# openmv3.net
KiCad netlist of a schematic drawn in EAGLE
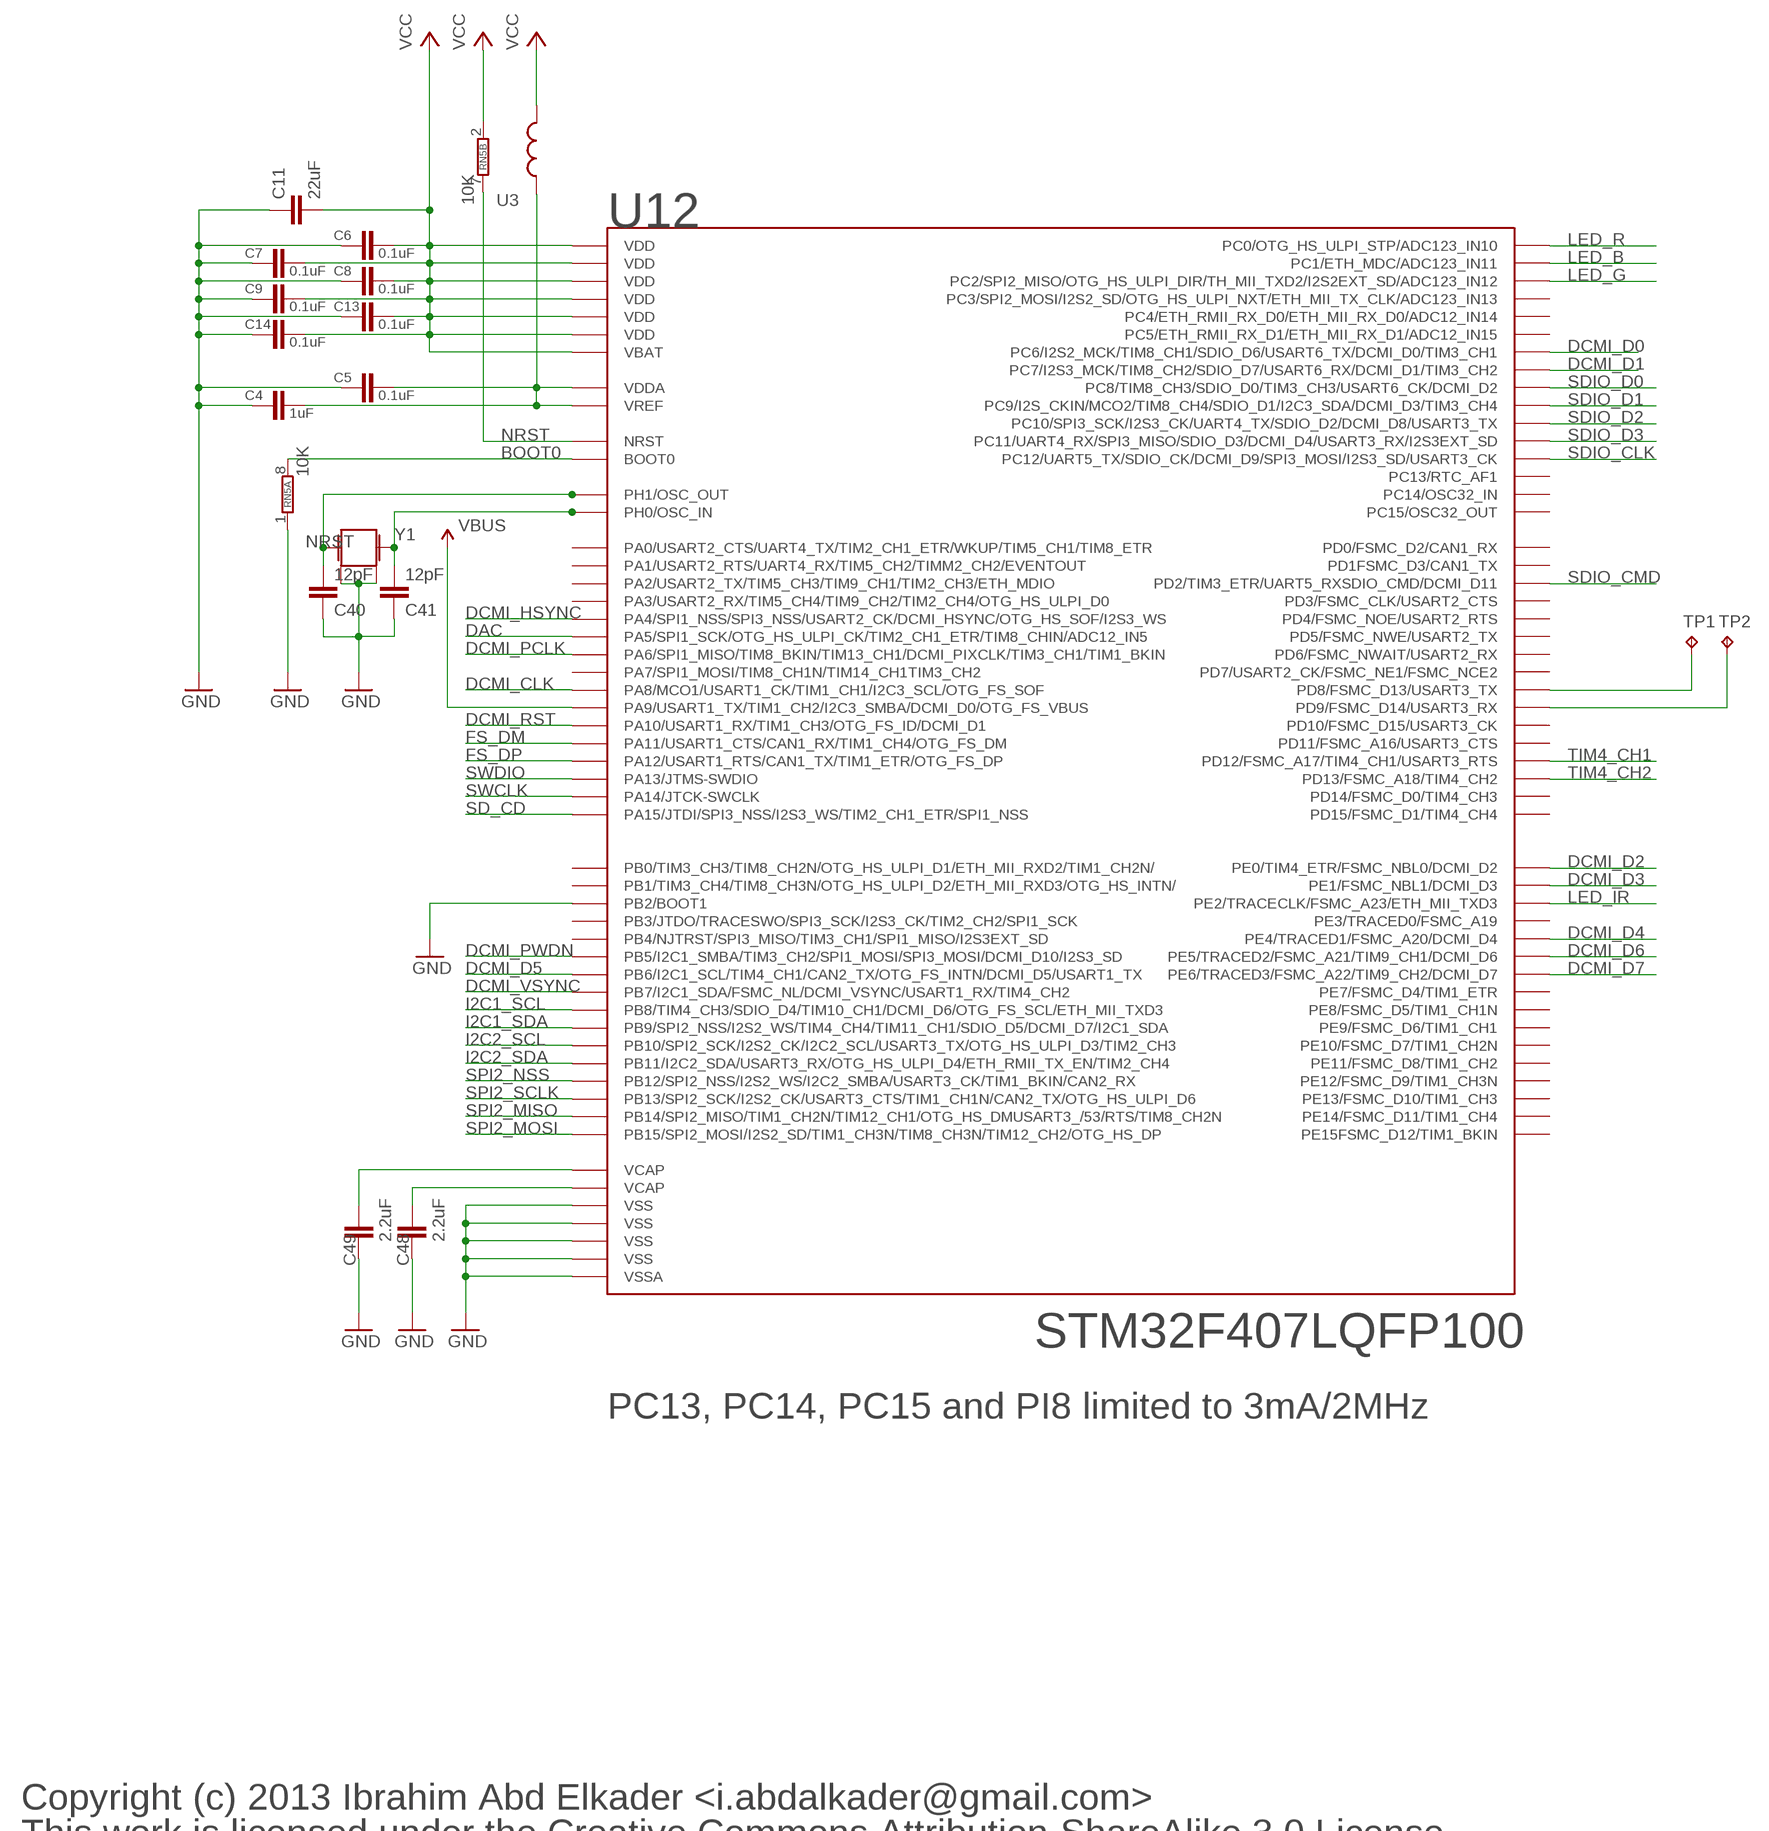
[diagram p0: schematic, sheet 1, part 1 of 2]
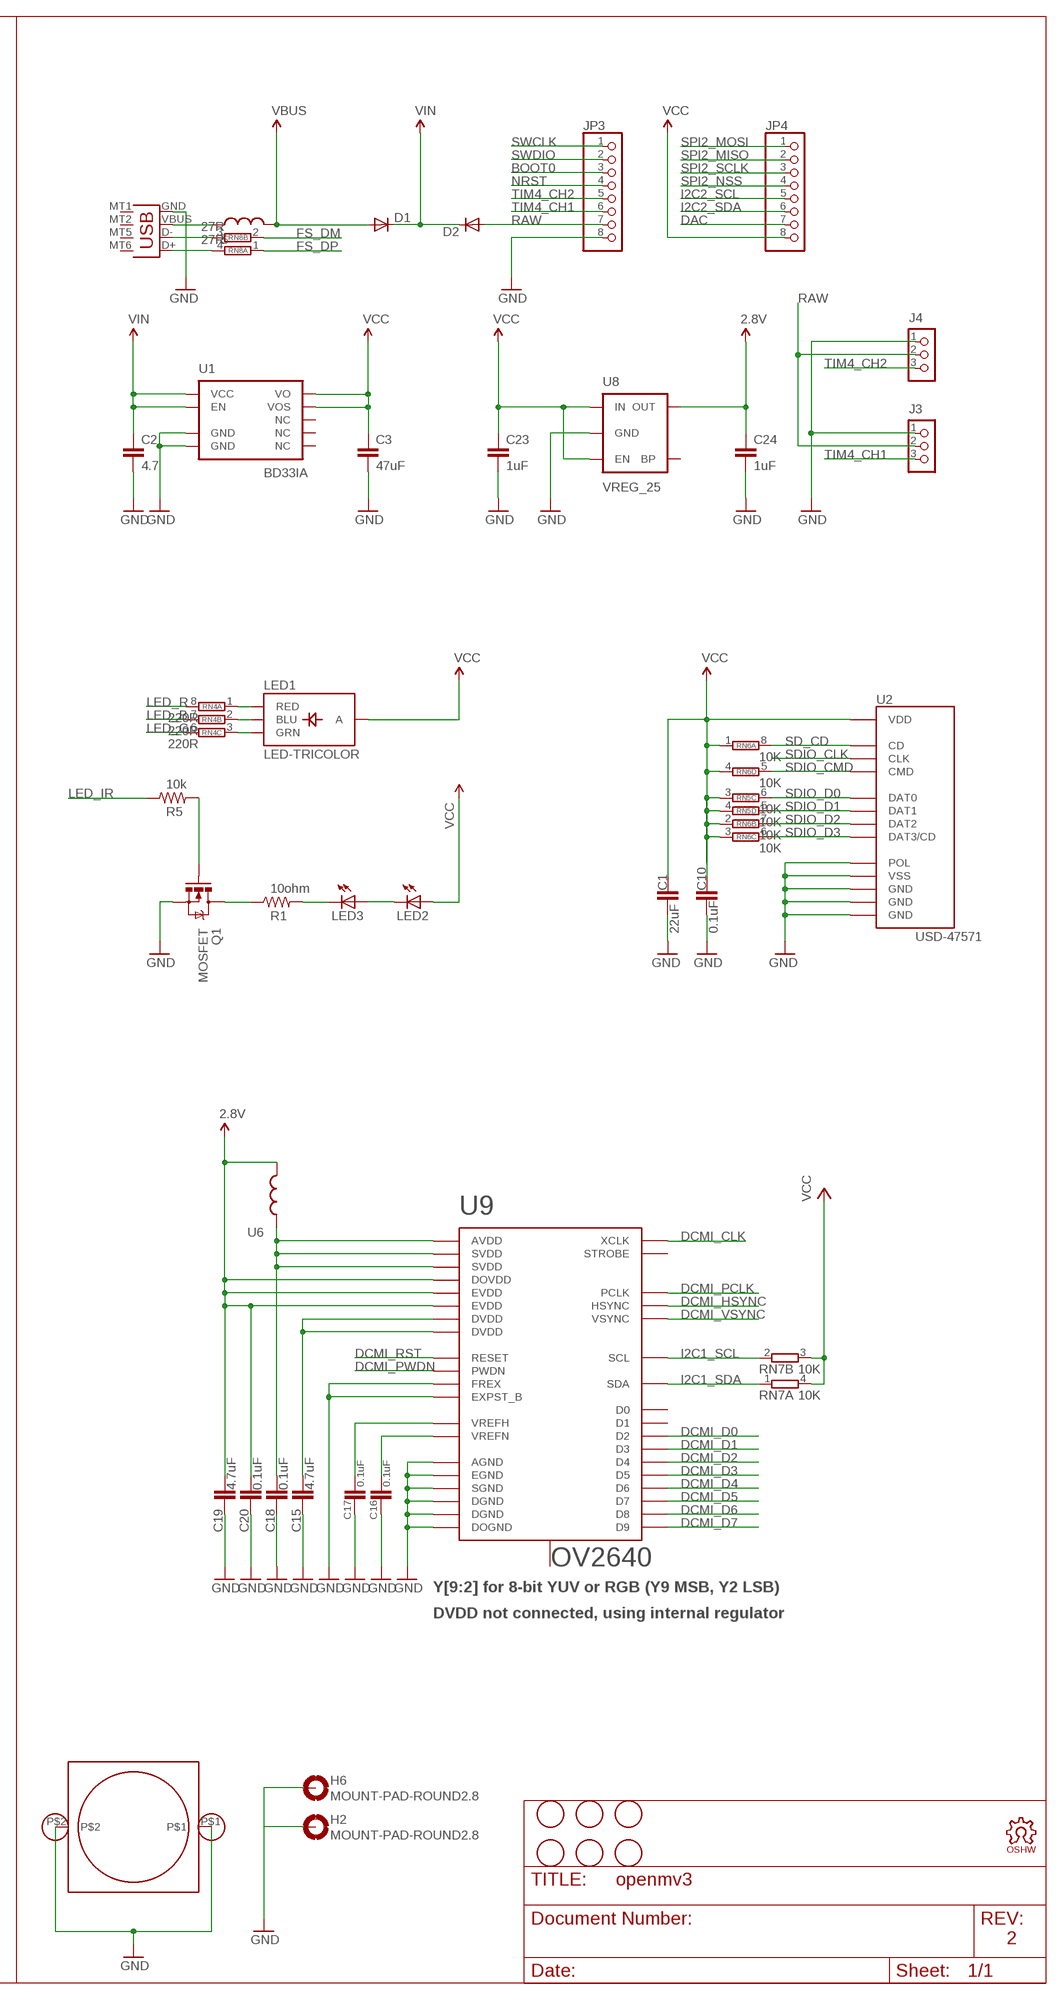
[diagram p1: schematic, sheet 1, part 2 of 2]

(export (version "E")
  (design (tool "Eeschema 10.0.6"))
  (components
    (comp (ref "C1")
      (value "22uF")
      (footprint "eagle-import:0805")
      (libsource (lib "eagle-import") (part "CAP0805"))
    )
    (comp (ref "C2")
      (value "4.7")
      (footprint "eagle-import:0603-CAP")
      (libsource (lib "eagle-import") (part "CAP0603-CAP"))
    )
    (comp (ref "C3")
      (value "47uF")
      (footprint "eagle-import:1206")
      (libsource (lib "eagle-import") (part "CAP1206"))
    )
    (comp (ref "C4")
      (value "1uF")
      (footprint "eagle-import:0603-CAP")
      (libsource (lib "eagle-import") (part "CAP0603-CAP"))
    )
    (comp (ref "C5")
      (value "0.1uF")
      (footprint "eagle-import:0603-CAP")
      (libsource (lib "eagle-import") (part "CAP0603-CAP"))
    )
    (comp (ref "C6")
      (value "0.1uF")
      (footprint "eagle-import:0603-CAP")
      (libsource (lib "eagle-import") (part "CAP0603-CAP"))
    )
    (comp (ref "C7")
      (value "0.1uF")
      (footprint "eagle-import:0603-CAP")
      (libsource (lib "eagle-import") (part "CAP0603-CAP"))
    )
    (comp (ref "C8")
      (value "0.1uF")
      (footprint "eagle-import:0603-CAP")
      (libsource (lib "eagle-import") (part "CAP0603-CAP"))
    )
    (comp (ref "C9")
      (value "0.1uF")
      (footprint "eagle-import:0603-CAP")
      (libsource (lib "eagle-import") (part "CAP0603-CAP"))
    )
    (comp (ref "C10")
      (value "0.1uF")
      (footprint "eagle-import:0603-CAP")
      (libsource (lib "eagle-import") (part "CAP0603-CAP"))
    )
    (comp (ref "C11")
      (value "22uF")
      (footprint "eagle-import:0805")
      (libsource (lib "eagle-import") (part "CAP0805"))
    )
    (comp (ref "C13")
      (value "0.1uF")
      (footprint "eagle-import:0603-CAP")
      (libsource (lib "eagle-import") (part "CAP0603-CAP"))
    )
    (comp (ref "C14")
      (value "0.1uF")
      (footprint "eagle-import:0603-CAP")
      (libsource (lib "eagle-import") (part "CAP0603-CAP"))
    )
    (comp (ref "C15")
      (value "4.7uF")
      (footprint "eagle-import:0603-CAP")
      (libsource (lib "eagle-import") (part "CAP0603-CAP"))
    )
    (comp (ref "C16")
      (value "0.1uF")
      (footprint "eagle-import:0603-CAP")
      (libsource (lib "eagle-import") (part "CAP0603-CAP"))
    )
    (comp (ref "C17")
      (value "0.1uF")
      (footprint "eagle-import:0603-CAP")
      (libsource (lib "eagle-import") (part "CAP0603-CAP"))
    )
    (comp (ref "C18")
      (value "0.1uF")
      (footprint "eagle-import:0603-CAP")
      (libsource (lib "eagle-import") (part "CAP0603-CAP"))
    )
    (comp (ref "C19")
      (value "4.7uF")
      (footprint "eagle-import:0603-CAP")
      (libsource (lib "eagle-import") (part "CAP0603-CAP"))
    )
    (comp (ref "C20")
      (value "0.1uF")
      (footprint "eagle-import:0603-CAP")
      (libsource (lib "eagle-import") (part "CAP0603-CAP"))
    )
    (comp (ref "C23")
      (value "1uF")
      (footprint "eagle-import:0603-CAP")
      (libsource (lib "eagle-import") (part "CAP0603-CAP"))
    )
    (comp (ref "C24")
      (value "1uF")
      (footprint "eagle-import:0603-CAP")
      (libsource (lib "eagle-import") (part "CAP0603-CAP"))
    )
    (comp (ref "C40")
      (value "12pF")
      (footprint "eagle-import:0603-CAP")
      (libsource (lib "eagle-import") (part "CAP0603-CAP"))
    )
    (comp (ref "C41")
      (value "12pF")
      (footprint "eagle-import:0603-CAP")
      (libsource (lib "eagle-import") (part "CAP0603-CAP"))
    )
    (comp (ref "C48")
      (value "2.2uF")
      (footprint "eagle-import:0603-CAP")
      (libsource (lib "eagle-import") (part "CAP0603-CAP"))
    )
    (comp (ref "C49")
      (value "2.2uF")
      (footprint "eagle-import:0603-CAP")
      (libsource (lib "eagle-import") (part "CAP0603-CAP"))
    )
    (comp (ref "D1")
      (value "DIODESOD")
      (footprint "eagle-import:SOD-323")
      (libsource (lib "eagle-import") (part "DIODESOD"))
    )
    (comp (ref "D2")
      (value "DIODESOD")
      (footprint "eagle-import:SOD-323")
      (libsource (lib "eagle-import") (part "DIODESOD"))
    )
    (comp (ref "H2")
      (value "MOUNT-PAD-ROUND2.8")
      (footprint "eagle-import:2,8-PAD")
      (libsource (lib "eagle-import") (part "MOUNT-PAD-ROUND2.8"))
    )
    (comp (ref "H6")
      (value "MOUNT-PAD-ROUND2.8")
      (footprint "eagle-import:2,8-PAD")
      (libsource (lib "eagle-import") (part "MOUNT-PAD-ROUND2.8"))
    )
    (comp (ref "J3")
      (value "CON_HEADER_1X03")
      (footprint "eagle-import:M1X3_SMD")
      (libsource (lib "eagle-import") (part "CON_HEADER_1X03"))
    )
    (comp (ref "J4")
      (value "CON_HEADER_1X03")
      (footprint "eagle-import:M1X3_SMD")
      (libsource (lib "eagle-import") (part "CON_HEADER_1X03"))
    )
    (comp (ref "JP3")
      (value "PINHD-1X8")
      (footprint "eagle-import:1X08")
      (libsource (lib "eagle-import") (part "PINHD-1X8"))
    )
    (comp (ref "JP4")
      (value "PINHD-1X8")
      (footprint "eagle-import:1X08")
      (libsource (lib "eagle-import") (part "PINHD-1X8"))
    )
    (comp (ref "LED1")
      (value "LED-TRICOLOR")
      (footprint "eagle-import:LED-TRICOLOR-SMD")
      (libsource (lib "eagle-import") (part "LED-TRICOLOR"))
    )
    (comp (ref "LED2")
      (value "LED3MM")
      (footprint "eagle-import:LED3MM")
      (libsource (lib "eagle-import") (part "LED3MM"))
    )
    (comp (ref "LED3")
      (value "LED3MM")
      (footprint "eagle-import:LED3MM")
      (libsource (lib "eagle-import") (part "LED3MM"))
    )
    (comp (ref "LOGO1")
      (value "OSHW_LOGO_FILLX0150-NT")
      (footprint "eagle-import:OSHW_FILLX150_NOTEXT")
      (libsource (lib "eagle-import") (part "OSHW_LOGO_FILLX0150-NT"))
    )
    (comp (ref "Q1")
      (value "MOSFET")
      (footprint "eagle-import:SOT23-3")
      (libsource (lib "eagle-import") (part "MOSFET-NCHANNELSMD"))
    )
    (comp (ref "R1")
      (value "10ohm")
      (footprint "eagle-import:0603-RES")
      (libsource (lib "eagle-import") (part "RESISTOR0603-RES"))
    )
    (comp (ref "R5")
      (value "10k")
      (footprint "eagle-import:0603-RES")
      (libsource (lib "eagle-import") (part "RESISTOR0603-RES"))
    )
    (comp (ref "RN4")
      (value "220R")
      (footprint "eagle-import:EXBV8V")
      (fields (field (name "OC_FARNELL") "unknown") (field (name "OC_NEWARK") "unknown"))
      (libsource (lib "eagle-import") (part "4R-NEXBV8V"))
    )
    (comp (ref "RN5")
      (value "10K")
      (footprint "eagle-import:EXBV8V")
      (fields (field (name "OC_FARNELL") "unknown") (field (name "OC_NEWARK") "unknown"))
      (libsource (lib "eagle-import") (part "4R-NEXBV8V"))
    )
    (comp (ref "RN6")
      (value "10K")
      (footprint "eagle-import:EXBV8V")
      (fields (field (name "OC_FARNELL") "unknown") (field (name "OC_NEWARK") "unknown"))
      (libsource (lib "eagle-import") (part "4R-NEXBV8V"))
    )
    (comp (ref "RN7")
      (value "10K")
      (footprint "eagle-import:EXBV4V")
      (libsource (lib "eagle-import") (part "2R-NEXBV4V"))
    )
    (comp (ref "RN8")
      (value "27R")
      (footprint "eagle-import:EXBV4V")
      (libsource (lib "eagle-import") (part "2R-NEXBV4V"))
    )
    (comp (ref "TP1")
      (value "TPTP12R")
      (footprint "eagle-import:TP12R")
      (libsource (lib "eagle-import") (part "TPTP12R"))
    )
    (comp (ref "TP2")
      (value "TPTP12R")
      (footprint "eagle-import:TP12R")
      (libsource (lib "eagle-import") (part "TPTP12R"))
    )
    (comp (ref "U$1")
      (value "LENSMOUNT20MM")
      (footprint "eagle-import:LENSMOUNT-20MM")
      (libsource (lib "eagle-import") (part "LENSMOUNT20MM"))
    )
    (comp (ref "U$14")
      (value "FIDUCIAL")
      (footprint "eagle-import:FIDUCIAL_1MM")
      (libsource (lib "eagle-import") (part "FIDUCIAL"))
    )
    (comp (ref "U$15")
      (value "FIDUCIAL")
      (footprint "eagle-import:FIDUCIAL_1MM")
      (libsource (lib "eagle-import") (part "FIDUCIAL"))
    )
    (comp (ref "U$16")
      (value "FIDUCIAL")
      (footprint "eagle-import:FIDUCIAL_1MM")
      (libsource (lib "eagle-import") (part "FIDUCIAL"))
    )
    (comp (ref "U$17")
      (value "FIDUCIAL")
      (footprint "eagle-import:FIDUCIAL_1MM")
      (libsource (lib "eagle-import") (part "FIDUCIAL"))
    )
    (comp (ref "U$19")
      (value "FIDUCIAL")
      (footprint "eagle-import:FIDUCIAL_1MM")
      (libsource (lib "eagle-import") (part "FIDUCIAL"))
    )
    (comp (ref "U$20")
      (value "FIDUCIAL")
      (footprint "eagle-import:FIDUCIAL_1MM")
      (libsource (lib "eagle-import") (part "FIDUCIAL"))
    )
    (comp (ref "U1")
      (value "BD33IA")
      (footprint "eagle-import:HTSOP-J8")
      (libsource (lib "eagle-import") (part "BD33IA"))
    )
    (comp (ref "U2")
      (value "USD-47571")
      (footprint "eagle-import:USD-47571")
      (libsource (lib "eagle-import") (part "USD-47571"))
    )
    (comp (ref "U3")
      (value "INDUCTOR0603")
      (footprint "eagle-import:0603")
      (libsource (lib "eagle-import") (part "INDUCTOR0603"))
    )
    (comp (ref "U6")
      (value "INDUCTOR0603")
      (footprint "eagle-import:0603")
      (libsource (lib "eagle-import") (part "INDUCTOR0603"))
    )
    (comp (ref "U7")
      (value "INDUCTOR0603")
      (footprint "eagle-import:0603")
      (libsource (lib "eagle-import") (part "INDUCTOR0603"))
    )
    (comp (ref "U8")
      (value "VREG_25")
      (footprint "eagle-import:SOT23-5")
      (libsource (lib "eagle-import") (part "V_REG_LDOSMD"))
    )
    (comp (ref "U9")
      (value "OV2640")
      (footprint "eagle-import:CSP2")
      (libsource (lib "eagle-import") (part "OV2640"))
    )
    (comp (ref "U12")
      (value "STM32F407LQFP100")
      (footprint "eagle-import:LQFP100")
      (libsource (lib "eagle-import") (part "STM32F407LQFP100"))
    )
    (comp (ref "X2")
      (value "USB-MICROB")
      (footprint "eagle-import:USB-MICROB")
      (libsource (lib "eagle-import") (part "USB-MICROB"))
    )
    (comp (ref "Y1")
      (value "CRYSTAL2.5X2.0")
      (footprint "eagle-import:CRYSTAL-2.5X2.0")
      (libsource (lib "eagle-import") (part "CRYSTAL2.5X2.0"))
    )
  )
  (nets
    (net (code "1") (name "/BOOT0") (class "Default")
      (node (ref "JP3") (pin "3") (pinfunction "3_3") (pintype "passive"))
      (node (ref "RN5") (pin "8") (pinfunction "2_8") (pintype "passive"))
      (node (ref "U12") (pin "94") (pinfunction "BOOT0_94") (pintype "bidirectional"))
    )
    (net (code "2") (name "/DAC") (class "Default")
      (node (ref "JP4") (pin "7") (pinfunction "7_7") (pintype "passive"))
      (node (ref "U12") (pin "30") (pinfunction "PA5/SPI1_SCK/OTG_HS_ULPI_CK/TIM2_CH1_ETR/TIM8_CHIN/ADC12_IN5_30") (pintype "bidirectional"))
    )
    (net (code "3") (name "/DCMI_CLK") (class "Default")
      (node (ref "U12") (pin "67") (pinfunction "PA8/MCO1/USART1_CK/TIM1_CH1/I2C3_SCL/OTG_FS_SOF_67") (pintype "bidirectional"))
      (node (ref "U9") (pin "C4") (pinfunction "XCLK_C4") (pintype "bidirectional"))
    )
    (net (code "4") (name "/DCMI_D0") (class "Default")
      (node (ref "U12") (pin "63") (pinfunction "PC6/I2S2_MCK/TIM8_CH1/SDIO_D6/USART6_TX/DCMI_D0/TIM3_CH1_63") (pintype "bidirectional"))
      (node (ref "U9") (pin "F3") (pinfunction "D2_F3") (pintype "bidirectional"))
    )
    (net (code "5") (name "/DCMI_D1") (class "Default")
      (node (ref "U12") (pin "64") (pinfunction "PC7/I2S3_MCK/TIM8_CH2/SDIO_D7/USART6_RX/DCMI_D1/TIM3_CH2_64") (pintype "bidirectional"))
      (node (ref "U9") (pin "G3") (pinfunction "D3_G3") (pintype "bidirectional"))
    )
    (net (code "6") (name "/DCMI_D2") (class "Default")
      (node (ref "U12") (pin "97") (pinfunction "PE0/TIM4_ETR/FSMC_NBL0/DCMI_D2_97") (pintype "bidirectional"))
      (node (ref "U9") (pin "F4") (pinfunction "D4_F4") (pintype "bidirectional"))
    )
    (net (code "7") (name "/DCMI_D3") (class "Default")
      (node (ref "U12") (pin "98") (pinfunction "PE1/FSMC_NBL1/DCMI_D3_98") (pintype "bidirectional"))
      (node (ref "U9") (pin "G4") (pinfunction "D5_G4") (pintype "bidirectional"))
    )
    (net (code "8") (name "/DCMI_D4") (class "Default")
      (node (ref "U12") (pin "3") (pinfunction "PE4/TRACED1/FSMC_A20/DCMI_D4_3") (pintype "bidirectional"))
      (node (ref "U9") (pin "E5") (pinfunction "D6_E5") (pintype "bidirectional"))
    )
    (net (code "9") (name "/DCMI_D5") (class "Default")
      (node (ref "U12") (pin "92") (pinfunction "PB6/I2C1_SCL/TIM4_CH1/CAN2_TX/OTG_FS_INTN/DCMI_D5/USART1_TX_92") (pintype "bidirectional"))
      (node (ref "U9") (pin "G5") (pinfunction "D7_G5") (pintype "bidirectional"))
    )
    (net (code "10") (name "/DCMI_D6") (class "Default")
      (node (ref "U12") (pin "4") (pinfunction "PE5/TRACED2/FSMC_A21/TIM9_CH1/DCMI_D6_4") (pintype "bidirectional"))
      (node (ref "U9") (pin "F5") (pinfunction "D8_F5") (pintype "bidirectional"))
    )
    (net (code "11") (name "/DCMI_D7") (class "Default")
      (node (ref "U12") (pin "5") (pinfunction "PE6/TRACED3/FSMC_A22/TIM9_CH2/DCMI_D7_5") (pintype "bidirectional"))
      (node (ref "U9") (pin "G6") (pinfunction "D9_G6") (pintype "bidirectional"))
    )
    (net (code "12") (name "/DCMI_HSYNC") (class "Default")
      (node (ref "U12") (pin "29") (pinfunction "PA4/SPI1_NSS/SPI3_NSS/USART2_CK/DCMI_HSYNC/OTG_HS_SOF/I2S3_WS_29") (pintype "bidirectional"))
      (node (ref "U9") (pin "C3") (pinfunction "HSYNC_C3") (pintype "bidirectional"))
    )
    (net (code "13") (name "/DCMI_PCLK") (class "Default")
      (node (ref "U12") (pin "31") (pinfunction "PA6/SPI1_MISO/TIM8_BKIN/TIM13_CH1/DCMI_PIXCLK/TIM3_CH1/TIM1_BKIN_31") (pintype "bidirectional"))
      (node (ref "U9") (pin "E3") (pinfunction "PCLK_E3") (pintype "bidirectional"))
    )
    (net (code "14") (name "/DCMI_PWDN") (class "Default")
      (node (ref "U12") (pin "91") (pinfunction "PB5/I2C1_SMBA/TIM3_CH2/SPI1_MOSI/SPI3_MOSI/DCMI_D10/I2S3_SD_91") (pintype "bidirectional"))
      (node (ref "U9") (pin "B6") (pinfunction "PWDN_B6") (pintype "bidirectional"))
    )
    (net (code "15") (name "/DCMI_RST") (class "Default")
      (node (ref "U12") (pin "69") (pinfunction "PA10/USART1_RX/TIM1_CH3/OTG_FS_ID/DCMI_D1_69") (pintype "bidirectional"))
      (node (ref "U9") (pin "C6") (pinfunction "RESET_C6") (pintype "bidirectional"))
    )
    (net (code "16") (name "/DCMI_VSYNC") (class "Default")
      (node (ref "U12") (pin "93") (pinfunction "PB7/I2C1_SDA/FSMC_NL/DCMI_VSYNC/USART1_RX/TIM4_CH2_93") (pintype "bidirectional"))
      (node (ref "U9") (pin "D2") (pinfunction "VSYNC_D2") (pintype "bidirectional"))
    )
    (net (code "17") (name "/FS_DM") (class "Default")
      (node (ref "RN8") (pin "2") (pinfunction "1_2") (pintype "passive"))
      (node (ref "U12") (pin "70") (pinfunction "PA11/USART1_CTS/CAN1_RX/TIM1_CH4/OTG_FS_DM_70") (pintype "bidirectional"))
    )
    (net (code "18") (name "/FS_DP") (class "Default")
      (node (ref "RN8") (pin "1") (pinfunction "1_1") (pintype "passive"))
      (node (ref "U12") (pin "71") (pinfunction "PA12/USART1_RTS/CAN1_TX/TIM1_ETR/OTG_FS_DP_71") (pintype "bidirectional"))
    )
    (net (code "19") (name "/I2C1_SCL") (class "Default")
      (node (ref "RN7") (pin "2") (pinfunction "1_2") (pintype "passive"))
      (node (ref "U12") (pin "95") (pinfunction "PB8/TIM4_CH3/SDIO_D4/TIM10_CH1/DCMI_D6/OTG_FS_SCL/ETH_MII_TXD3_95") (pintype "bidirectional"))
      (node (ref "U9") (pin "C2") (pinfunction "SCL_C2") (pintype "bidirectional"))
    )
    (net (code "20") (name "/I2C1_SDA") (class "Default")
      (node (ref "RN7") (pin "1") (pinfunction "1_1") (pintype "passive"))
      (node (ref "U12") (pin "96") (pinfunction "PB9/SPI2_NSS/I2S2_WS/TIM4_CH4/TIM11_CH1/SDIO_D5/DCMI_D7/I2C1_SDA_96") (pintype "bidirectional"))
      (node (ref "U9") (pin "C1") (pinfunction "SDA_C1") (pintype "bidirectional"))
    )
    (net (code "21") (name "/I2C2_SCL") (class "Default")
      (node (ref "JP4") (pin "5") (pinfunction "5_5") (pintype "passive"))
      (node (ref "U12") (pin "47") (pinfunction "PB10/SPI2_SCK/I2S2_CK/I2C2_SCL/USART3_TX/OTG_HS_ULPI_D3/TIM2_CH3_47") (pintype "bidirectional"))
    )
    (net (code "22") (name "/I2C2_SDA") (class "Default")
      (node (ref "JP4") (pin "6") (pinfunction "6_6") (pintype "passive"))
      (node (ref "U12") (pin "48") (pinfunction "PB11/I2C2_SDA/USART3_RX/OTG_HS_ULPI_D4/ETH_RMII_TX_EN/TIM2_CH4_48") (pintype "bidirectional"))
    )
    (net (code "23") (name "/LED_B") (class "Default")
      (node (ref "RN4") (pin "7") (pinfunction "2_7") (pintype "passive"))
      (node (ref "U12") (pin "16") (pinfunction "PC1/ETH_MDC/ADC123_IN11_16") (pintype "bidirectional"))
    )
    (net (code "24") (name "/LED_G") (class "Default")
      (node (ref "RN4") (pin "6") (pinfunction "2_6") (pintype "passive"))
      (node (ref "U12") (pin "17") (pinfunction "PC2/SPI2_MISO/OTG_HS_ULPI_DIR/TH_MII_TXD2/I2S2EXT_SD/ADC123_IN12_17") (pintype "bidirectional"))
    )
    (net (code "25") (name "/LED_IR") (class "Default")
      (node (ref "R5") (pin "1") (pinfunction "1_1") (pintype "passive"))
      (node (ref "U12") (pin "1") (pinfunction "PE2/TRACECLK/FSMC_A23/ETH_MII_TXD3_1") (pintype "bidirectional"))
    )
    (net (code "26") (name "/LED_R") (class "Default")
      (node (ref "RN4") (pin "8") (pinfunction "2_8") (pintype "passive"))
      (node (ref "U12") (pin "15") (pinfunction "PC0/OTG_HS_ULPI_STP/ADC123_IN10_15") (pintype "bidirectional"))
    )
    (net (code "27") (name "/NRST") (class "Default")
      (node (ref "JP3") (pin "4") (pinfunction "4_4") (pintype "passive"))
      (node (ref "RN5") (pin "7") (pinfunction "2_7") (pintype "passive"))
      (node (ref "U12") (pin "14") (pinfunction "NRST_14") (pintype "bidirectional"))
    )
    (net (code "28") (name "/RAW") (class "Default")
      (node (ref "D2") (pin "2") (pinfunction "A_2") (pintype "passive"))
      (node (ref "J3") (pin "2") (pinfunction "2_2") (pintype "bidirectional"))
      (node (ref "J4") (pin "2") (pinfunction "2_2") (pintype "bidirectional"))
      (node (ref "JP3") (pin "7") (pinfunction "7_7") (pintype "passive"))
    )
    (net (code "29") (name "/SDIO_CLK") (class "Default")
      (node (ref "U12") (pin "80") (pinfunction "PC12/UART5_TX/SDIO_CK/DCMI_D9/SPI3_MOSI/I2S3_SD/USART3_CK_80") (pintype "bidirectional"))
      (node (ref "U2") (pin "P$5") (pinfunction "CLK_P$5") (pintype "bidirectional"))
    )
    (net (code "30") (name "/SDIO_CMD") (class "Default")
      (node (ref "RN6") (pin "5") (pinfunction "2_5") (pintype "passive"))
      (node (ref "U12") (pin "83") (pinfunction "PD2/TIM3_ETR/UART5_RXSDIO_CMD/DCMI_D11_83") (pintype "bidirectional"))
      (node (ref "U2") (pin "P$3") (pinfunction "CMD_P$3") (pintype "bidirectional"))
    )
    (net (code "31") (name "/SDIO_D0") (class "Default")
      (node (ref "RN5") (pin "6") (pinfunction "2_6") (pintype "passive"))
      (node (ref "U12") (pin "65") (pinfunction "PC8/TIM8_CH3/SDIO_D0/TIM3_CH3/USART6_CK/DCMI_D2_65") (pintype "bidirectional"))
      (node (ref "U2") (pin "P$7") (pinfunction "DAT0_P$7") (pintype "bidirectional"))
    )
    (net (code "32") (name "/SDIO_D1") (class "Default")
      (node (ref "RN5") (pin "5") (pinfunction "2_5") (pintype "passive"))
      (node (ref "U12") (pin "66") (pinfunction "PC9/I2S_CKIN/MCO2/TIM8_CH4/SDIO_D1/I2C3_SDA/DCMI_D3/TIM3_CH4_66") (pintype "bidirectional"))
      (node (ref "U2") (pin "P$8") (pinfunction "DAT1_P$8") (pintype "bidirectional"))
    )
    (net (code "33") (name "/SDIO_D2") (class "Default")
      (node (ref "RN6") (pin "7") (pinfunction "2_7") (pintype "passive"))
      (node (ref "U12") (pin "78") (pinfunction "PC10/SPI3_SCK/I2S3_CK/UART4_TX/SDIO_D2/DCMI_D8/USART3_TX_78") (pintype "bidirectional"))
      (node (ref "U2") (pin "P$1") (pinfunction "DAT2_P$1") (pintype "bidirectional"))
    )
    (net (code "34") (name "/SDIO_D3") (class "Default")
      (node (ref "RN6") (pin "6") (pinfunction "2_6") (pintype "passive"))
      (node (ref "U12") (pin "79") (pinfunction "PC11/UART4_RX/SPI3_MISO/SDIO_D3/DCMI_D4/USART3_RX/I2S3EXT_SD_79") (pintype "bidirectional"))
      (node (ref "U2") (pin "P$2") (pinfunction "DAT3/CD_P$2") (pintype "bidirectional"))
    )
    (net (code "35") (name "/SD_CD") (class "Default")
      (node (ref "RN6") (pin "8") (pinfunction "2_8") (pintype "passive"))
      (node (ref "U12") (pin "77") (pinfunction "PA15/JTDI/SPI3_NSS/I2S3_WS/TIM2_CH1_ETR/SPI1_NSS_77") (pintype "bidirectional"))
      (node (ref "U2") (pin "G$5") (pinfunction "CD_G$5") (pintype "power_in"))
    )
    (net (code "36") (name "/SPI2_MISO") (class "Default")
      (node (ref "JP4") (pin "2") (pinfunction "2_2") (pintype "passive"))
      (node (ref "U12") (pin "53") (pinfunction "PB14/SPI2_MISO/TIM1_CH2N/TIM12_CH1/OTG_HS_DMUSART3_/53/RTS/TIM8_CH2N_53") (pintype "bidirectional"))
    )
    (net (code "37") (name "/SPI2_MOSI") (class "Default")
      (node (ref "JP4") (pin "1") (pinfunction "1_1") (pintype "passive"))
      (node (ref "U12") (pin "54") (pinfunction "PB15/SPI2_MOSI/I2S2_SD/TIM1_CH3N/TIM8_CH3N/TIM12_CH2/OTG_HS_DP_54") (pintype "bidirectional"))
    )
    (net (code "38") (name "/SPI2_NSS") (class "Default")
      (node (ref "JP4") (pin "4") (pinfunction "4_4") (pintype "passive"))
      (node (ref "U12") (pin "51") (pinfunction "PB12/SPI2_NSS/I2S2_WS/I2C2_SMBA/USART3_CK/TIM1_BKIN/CAN2_RX_51") (pintype "bidirectional"))
    )
    (net (code "39") (name "/SPI2_SCLK") (class "Default")
      (node (ref "JP4") (pin "3") (pinfunction "3_3") (pintype "passive"))
      (node (ref "U12") (pin "52") (pinfunction "PB13/SPI2_SCK/I2S2_CK/USART3_CTS/TIM1_CH1N/CAN2_TX/OTG_HS_ULPI_D6_52") (pintype "bidirectional"))
    )
    (net (code "40") (name "/SWCLK") (class "Default")
      (node (ref "JP3") (pin "1") (pinfunction "1_1") (pintype "passive"))
      (node (ref "U12") (pin "76") (pinfunction "PA14/JTCK-SWCLK_76") (pintype "bidirectional"))
    )
    (net (code "41") (name "/SWDIO") (class "Default")
      (node (ref "JP3") (pin "2") (pinfunction "2_2") (pintype "passive"))
      (node (ref "U12") (pin "72") (pinfunction "PA13/JTMS-SWDIO_72") (pintype "bidirectional"))
    )
    (net (code "42") (name "/TIM4_CH1") (class "Default")
      (node (ref "J3") (pin "3") (pinfunction "3_3") (pintype "bidirectional"))
      (node (ref "JP3") (pin "6") (pinfunction "6_6") (pintype "passive"))
      (node (ref "U12") (pin "59") (pinfunction "PD12/FSMC_A17/TIM4_CH1/USART3_RTS_59") (pintype "bidirectional"))
    )
    (net (code "43") (name "/TIM4_CH2") (class "Default")
      (node (ref "J4") (pin "3") (pinfunction "3_3") (pintype "bidirectional"))
      (node (ref "JP3") (pin "5") (pinfunction "5_5") (pintype "passive"))
      (node (ref "U12") (pin "60") (pinfunction "PD13/FSMC_A18/TIM4_CH2_60") (pintype "bidirectional"))
    )
    (net (code "44") (name "2.8V") (class "Default")
      (node (ref "C19") (pin "1") (pinfunction "1_1") (pintype "passive"))
      (node (ref "C20") (pin "1") (pinfunction "1_1") (pintype "passive"))
      (node (ref "C24") (pin "1") (pinfunction "1_1") (pintype "passive"))
      (node (ref "U6") (pin "2") (pinfunction "2_2") (pintype "passive"))
      (node (ref "U8") (pin "5") (pinfunction "OUT_5") (pintype "passive"))
      (node (ref "U9") (pin "B1") (pinfunction "DOVDD_B1") (pintype "power_in"))
      (node (ref "U9") (pin "F1") (pinfunction "EVDD_F1") (pintype "power_in"))
      (node (ref "U9") (pin "G1") (pinfunction "EVDD_G1") (pintype "power_in"))
    )
    (net (code "45") (name "GND") (class "Default")
      (node (ref "C1") (pin "2") (pinfunction "2_2") (pintype "passive"))
      (node (ref "C10") (pin "2") (pinfunction "2_2") (pintype "passive"))
      (node (ref "C11") (pin "1") (pinfunction "1_1") (pintype "passive"))
      (node (ref "C13") (pin "2") (pinfunction "2_2") (pintype "passive"))
      (node (ref "C14") (pin "2") (pinfunction "2_2") (pintype "passive"))
      (node (ref "C15") (pin "2") (pinfunction "2_2") (pintype "passive"))
      (node (ref "C16") (pin "2") (pinfunction "2_2") (pintype "passive"))
      (node (ref "C17") (pin "2") (pinfunction "2_2") (pintype "passive"))
      (node (ref "C18") (pin "2") (pinfunction "2_2") (pintype "passive"))
      (node (ref "C19") (pin "2") (pinfunction "2_2") (pintype "passive"))
      (node (ref "C2") (pin "2") (pinfunction "2_2") (pintype "passive"))
      (node (ref "C20") (pin "2") (pinfunction "2_2") (pintype "passive"))
      (node (ref "C23") (pin "2") (pinfunction "2_2") (pintype "passive"))
      (node (ref "C24") (pin "2") (pinfunction "2_2") (pintype "passive"))
      (node (ref "C3") (pin "2") (pinfunction "2_2") (pintype "passive"))
      (node (ref "C4") (pin "2") (pinfunction "2_2") (pintype "passive"))
      (node (ref "C40") (pin "1") (pinfunction "1_1") (pintype "passive"))
      (node (ref "C41") (pin "1") (pinfunction "1_1") (pintype "passive"))
      (node (ref "C48") (pin "2") (pinfunction "2_2") (pintype "passive"))
      (node (ref "C49") (pin "2") (pinfunction "2_2") (pintype "passive"))
      (node (ref "C5") (pin "2") (pinfunction "2_2") (pintype "passive"))
      (node (ref "C6") (pin "2") (pinfunction "2_2") (pintype "passive"))
      (node (ref "C7") (pin "2") (pinfunction "2_2") (pintype "passive"))
      (node (ref "C8") (pin "2") (pinfunction "2_2") (pintype "passive"))
      (node (ref "C9") (pin "2") (pinfunction "2_2") (pintype "passive"))
      (node (ref "H2") (pin "B2,8") (pinfunction "MOUNT_B2,8") (pintype "passive"))
      (node (ref "H6") (pin "B2,8") (pinfunction "MOUNT_B2,8") (pintype "passive"))
      (node (ref "J3") (pin "1") (pinfunction "1_1") (pintype "bidirectional"))
      (node (ref "J4") (pin "1") (pinfunction "1_1") (pintype "bidirectional"))
      (node (ref "JP3") (pin "8") (pinfunction "8_8") (pintype "passive"))
      (node (ref "Q1") (pin "2") (pinfunction "S_2") (pintype "passive"))
      (node (ref "RN5") (pin "1") (pinfunction "1_1") (pintype "passive"))
      (node (ref "U$1") (pin "P$1") (pinfunction "P$1_P$1") (pintype "power_in"))
      (node (ref "U$1") (pin "P$2") (pinfunction "P$2_P$2") (pintype "power_in"))
      (node (ref "U1") (pin "3") (pinfunction "GND_3") (pintype "input"))
      (node (ref "U1") (pin "P$1") (pinfunction "GND_P$1") (pintype "input"))
      (node (ref "U12") (pin "10") (pinfunction "VSS_10") (pintype "power_in"))
      (node (ref "U12") (pin "20") (pinfunction "VSSA_20") (pintype "power_in"))
      (node (ref "U12") (pin "27") (pinfunction "VSS_27") (pintype "power_in"))
      (node (ref "U12") (pin "37") (pinfunction "PB2/BOOT1_37") (pintype "bidirectional"))
      (node (ref "U12") (pin "74") (pinfunction "VSS_74") (pintype "power_in"))
      (node (ref "U12") (pin "99") (pinfunction "VSS_99") (pintype "power_in"))
      (node (ref "U2") (pin "G$1") (pinfunction "GND_G$1") (pintype "power_in"))
      (node (ref "U2") (pin "G$2") (pinfunction "GND_G$2") (pintype "power_in"))
      (node (ref "U2") (pin "G$3") (pinfunction "GND_G$3") (pintype "power_in"))
      (node (ref "U2") (pin "G$4") (pinfunction "POL_G$4") (pintype "power_in"))
      (node (ref "U2") (pin "P$6") (pinfunction "VSS_P$6") (pintype "power_in"))
      (node (ref "U8") (pin "2") (pinfunction "GND_2") (pintype "input"))
      (node (ref "U9") (pin "A1") (pinfunction "DOGND_A1") (pintype "power_in"))
      (node (ref "U9") (pin "A2") (pinfunction "EXPST_B_A2") (pintype "output"))
      (node (ref "U9") (pin "A3") (pinfunction "AGND_A3") (pintype "power_in"))
      (node (ref "U9") (pin "A4") (pinfunction "SGND_A4") (pintype "power_in"))
      (node (ref "U9") (pin "B2") (pinfunction "FREX_B2") (pintype "input"))
      (node (ref "U9") (pin "E4") (pinfunction "EGND_E4") (pintype "power_in"))
      (node (ref "U9") (pin "E6") (pinfunction "DGND_E6") (pintype "power_in"))
      (node (ref "U9") (pin "G2") (pinfunction "DGND_G2") (pintype "power_in"))
      (node (ref "X2") (pin "GND") (pinfunction "GND_GND") (pintype "bidirectional"))
      (node (ref "Y1") (pin "2") (pinfunction "P$1_2") (pintype "power_in"))
      (node (ref "Y1") (pin "4") (pinfunction "P$2_4") (pintype "power_in"))
    )
    (net (code "46") (name "Net-(C15-Pad1)") (class "Default")
      (node (ref "C15") (pin "1") (pinfunction "1_1") (pintype "passive"))
      (node (ref "U9") (pin "F2") (pinfunction "DVDD_F2") (pintype "power_in"))
      (node (ref "U9") (pin "F6") (pinfunction "DVDD_F6") (pintype "power_in"))
    )
    (net (code "47") (name "Net-(C48-Pad1)") (class "Default")
      (node (ref "C48") (pin "1") (pinfunction "1_1") (pintype "passive"))
      (node (ref "U12") (pin "73") (pinfunction "VCAP_73") (pintype "power_in"))
    )
    (net (code "48") (name "Net-(C49-Pad1)") (class "Default")
      (node (ref "C49") (pin "1") (pinfunction "1_1") (pintype "passive"))
      (node (ref "U12") (pin "49") (pinfunction "VCAP_49") (pintype "power_in"))
    )
    (net (code "49") (name "Net-(LED1-BLU)") (class "Default")
      (node (ref "LED1") (pin "B") (pinfunction "BLU_B") (pintype "bidirectional"))
      (node (ref "RN4") (pin "2") (pinfunction "1_2") (pintype "passive"))
    )
    (net (code "50") (name "Net-(LED1-GRN)") (class "Default")
      (node (ref "LED1") (pin "G") (pinfunction "GRN_G") (pintype "bidirectional"))
      (node (ref "RN4") (pin "3") (pinfunction "1_3") (pintype "passive"))
    )
    (net (code "51") (name "Net-(LED1-RED)") (class "Default")
      (node (ref "LED1") (pin "R") (pinfunction "RED_R") (pintype "bidirectional"))
      (node (ref "RN4") (pin "1") (pinfunction "1_1") (pintype "passive"))
    )
    (net (code "52") (name "Net-(LED2-C)") (class "Default")
      (node (ref "LED2") (pin "K") (pinfunction "C_K") (pintype "passive"))
      (node (ref "LED3") (pin "A") (pinfunction "A_A") (pintype "passive"))
    )
    (net (code "53") (name "Net-(LED3-C)") (class "Default")
      (node (ref "LED3") (pin "K") (pinfunction "C_K") (pintype "passive"))
      (node (ref "R1") (pin "2") (pinfunction "2_2") (pintype "passive"))
    )
    (net (code "54") (name "Net-(Q1-D)") (class "Default")
      (node (ref "Q1") (pin "3") (pinfunction "D_3") (pintype "passive"))
      (node (ref "R1") (pin "1") (pinfunction "1_1") (pintype "passive"))
    )
    (net (code "55") (name "Net-(Q1-G)") (class "Default")
      (node (ref "Q1") (pin "1") (pinfunction "G_1") (pintype "passive"))
      (node (ref "R5") (pin "2") (pinfunction "2_2") (pintype "passive"))
    )
    (net (code "56") (name "Net-(RN8A-2)") (class "Default")
      (node (ref "RN8") (pin "4") (pinfunction "2_4") (pintype "passive"))
      (node (ref "X2") (pin "D+") (pinfunction "D+_D+") (pintype "bidirectional"))
    )
    (net (code "57") (name "Net-(RN8B-2)") (class "Default")
      (node (ref "RN8") (pin "3") (pinfunction "2_3") (pintype "passive"))
      (node (ref "X2") (pin "D-") (pinfunction "D-_D-") (pintype "bidirectional"))
    )
    (net (code "58") (name "Net-(U7-Pad1)") (class "Default")
      (node (ref "U7") (pin "1") (pinfunction "1_1") (pintype "passive"))
      (node (ref "X2") (pin "VBUS") (pinfunction "VBUS_VBUS") (pintype "bidirectional"))
    )
    (net (code "59") (name "Net-(U9-AVDD)") (class "Default")
      (node (ref "C18") (pin "1") (pinfunction "1_1") (pintype "passive"))
      (node (ref "U6") (pin "1") (pinfunction "1_1") (pintype "passive"))
      (node (ref "U9") (pin "B3") (pinfunction "AVDD_B3") (pintype "power_in"))
      (node (ref "U9") (pin "B4") (pinfunction "SVDD_B4") (pintype "power_in"))
      (node (ref "U9") (pin "B5") (pinfunction "SVDD_B5") (pintype "power_in"))
    )
    (net (code "60") (name "Net-(U9-VREFH)") (class "Default")
      (node (ref "C17") (pin "1") (pinfunction "1_1") (pintype "passive"))
      (node (ref "U9") (pin "C5") (pinfunction "VREFH_C5") (pintype "power_in"))
    )
    (net (code "61") (name "Net-(U9-VREFN)") (class "Default")
      (node (ref "C16") (pin "1") (pinfunction "1_1") (pintype "passive"))
      (node (ref "U9") (pin "A5") (pinfunction "VREFN_A5") (pintype "power_in"))
    )
    (net (code "62") (name "Net-(U12-PD8{slash}FSMC_D13{slash}USART3_TX)") (class "Default")
      (node (ref "TP1") (pin "TP") (pinfunction "TP_TP") (pintype "input"))
      (node (ref "U12") (pin "55") (pinfunction "PD8/FSMC_D13/USART3_TX_55") (pintype "bidirectional"))
    )
    (net (code "63") (name "Net-(U12-PD9{slash}FSMC_D14{slash}USART3_RX)") (class "Default")
      (node (ref "TP2") (pin "TP") (pinfunction "TP_TP") (pintype "input"))
      (node (ref "U12") (pin "56") (pinfunction "PD9/FSMC_D14/USART3_RX_56") (pintype "bidirectional"))
    )
    (net (code "64") (name "Net-(U12-PH0{slash}OSC_IN)") (class "Default")
      (node (ref "C41") (pin "2") (pinfunction "2_2") (pintype "passive"))
      (node (ref "U12") (pin "12") (pinfunction "PH0/OSC_IN_12") (pintype "bidirectional"))
      (node (ref "Y1") (pin "1") (pinfunction "1_1") (pintype "passive"))
    )
    (net (code "65") (name "Net-(U12-PH1{slash}OSC_OUT)") (class "Default")
      (node (ref "C40") (pin "2") (pinfunction "2_2") (pintype "passive"))
      (node (ref "U12") (pin "13") (pinfunction "PH1/OSC_OUT_13") (pintype "bidirectional"))
      (node (ref "Y1") (pin "3") (pinfunction "2_3") (pintype "passive"))
    )
    (net (code "66") (name "Net-(U12-VDDA)") (class "Default")
      (node (ref "C4") (pin "1") (pinfunction "1_1") (pintype "passive"))
      (node (ref "C5") (pin "1") (pinfunction "1_1") (pintype "passive"))
      (node (ref "U12") (pin "21") (pinfunction "VREF_21") (pintype "power_in"))
      (node (ref "U12") (pin "22") (pinfunction "VDDA_22") (pintype "power_in"))
      (node (ref "U3") (pin "1") (pinfunction "1_1") (pintype "passive"))
    )
    (net (code "67") (name "VBUS") (class "Default")
      (node (ref "D1") (pin "2") (pinfunction "A_2") (pintype "passive"))
      (node (ref "U12") (pin "68") (pinfunction "PA9/USART1_TX/TIM1_CH2/I2C3_SMBA/DCMI_D0/OTG_FS_VBUS_68") (pintype "bidirectional"))
      (node (ref "U7") (pin "2") (pinfunction "2_2") (pintype "passive"))
    )
    (net (code "68") (name "VCC") (class "Default")
      (node (ref "C1") (pin "1") (pinfunction "1_1") (pintype "passive"))
      (node (ref "C10") (pin "1") (pinfunction "1_1") (pintype "passive"))
      (node (ref "C11") (pin "2") (pinfunction "2_2") (pintype "passive"))
      (node (ref "C13") (pin "1") (pinfunction "1_1") (pintype "passive"))
      (node (ref "C14") (pin "1") (pinfunction "1_1") (pintype "passive"))
      (node (ref "C23") (pin "1") (pinfunction "1_1") (pintype "passive"))
      (node (ref "C3") (pin "1") (pinfunction "1_1") (pintype "passive"))
      (node (ref "C6") (pin "1") (pinfunction "1_1") (pintype "passive"))
      (node (ref "C7") (pin "1") (pinfunction "1_1") (pintype "passive"))
      (node (ref "C8") (pin "1") (pinfunction "1_1") (pintype "passive"))
      (node (ref "C9") (pin "1") (pinfunction "1_1") (pintype "passive"))
      (node (ref "JP4") (pin "8") (pinfunction "8_8") (pintype "passive"))
      (node (ref "LED1") (pin "A") (pinfunction "A_A") (pintype "bidirectional"))
      (node (ref "LED2") (pin "A") (pinfunction "A_A") (pintype "passive"))
      (node (ref "RN5") (pin "2") (pinfunction "1_2") (pintype "passive"))
      (node (ref "RN5") (pin "3") (pinfunction "1_3") (pintype "passive"))
      (node (ref "RN5") (pin "4") (pinfunction "1_4") (pintype "passive"))
      (node (ref "RN6") (pin "1") (pinfunction "1_1") (pintype "passive"))
      (node (ref "RN6") (pin "2") (pinfunction "1_2") (pintype "passive"))
      (node (ref "RN6") (pin "3") (pinfunction "1_3") (pintype "passive"))
      (node (ref "RN6") (pin "4") (pinfunction "1_4") (pintype "passive"))
      (node (ref "RN7") (pin "3") (pinfunction "2_3") (pintype "passive"))
      (node (ref "RN7") (pin "4") (pinfunction "2_4") (pintype "passive"))
      (node (ref "U1") (pin "1") (pinfunction "VO_1") (pintype "output"))
      (node (ref "U1") (pin "2") (pinfunction "VOS_2") (pintype "output"))
      (node (ref "U12") (pin "100") (pinfunction "VDD_100") (pintype "power_in"))
      (node (ref "U12") (pin "11") (pinfunction "VDD_11") (pintype "power_in"))
      (node (ref "U12") (pin "19") (pinfunction "VDD_19") (pintype "power_in"))
      (node (ref "U12") (pin "28") (pinfunction "VDD_28") (pintype "power_in"))
      (node (ref "U12") (pin "50") (pinfunction "VDD_50") (pintype "power_in"))
      (node (ref "U12") (pin "6") (pinfunction "VBAT_6") (pintype "power_in"))
      (node (ref "U12") (pin "75") (pinfunction "VDD_75") (pintype "power_in"))
      (node (ref "U2") (pin "P$4") (pinfunction "VDD_P$4") (pintype "power_in"))
      (node (ref "U3") (pin "2") (pinfunction "2_2") (pintype "passive"))
      (node (ref "U8") (pin "1") (pinfunction "IN_1") (pintype "input"))
      (node (ref "U8") (pin "3") (pinfunction "EN_3") (pintype "input"))
    )
    (net (code "69") (name "VIN") (class "Default")
      (node (ref "C2") (pin "1") (pinfunction "1_1") (pintype "passive"))
      (node (ref "D1") (pin "1") (pinfunction "C_1") (pintype "passive"))
      (node (ref "D2") (pin "1") (pinfunction "C_1") (pintype "passive"))
      (node (ref "U1") (pin "5") (pinfunction "EN_5") (pintype "input"))
      (node (ref "U1") (pin "8") (pinfunction "VCC_8") (pintype "input"))
    )
    (net (code "70") (name "unconnected-(U1-NC-Pad4)") (class "Default")
      (node (ref "U1") (pin "4") (pinfunction "NC_4") (pintype "input"))
    )
    (net (code "71") (name "unconnected-(U1-NC-Pad6)") (class "Default")
      (node (ref "U1") (pin "6") (pinfunction "NC_6") (pintype "bidirectional"))
    )
    (net (code "72") (name "unconnected-(U1-NC-Pad7)") (class "Default")
      (node (ref "U1") (pin "7") (pinfunction "NC_7") (pintype "input"))
    )
    (net (code "73") (name "unconnected-(U8-BP-Pad4)") (class "Default")
      (node (ref "U8") (pin "4") (pinfunction "BP_4") (pintype "input"))
    )
    (net (code "74") (name "unconnected-(U9-D0-PadE2)") (class "Default")
      (node (ref "U9") (pin "E2") (pinfunction "D0_E2") (pintype "bidirectional"))
    )
    (net (code "75") (name "unconnected-(U9-D1-PadE1)") (class "Default")
      (node (ref "U9") (pin "E1") (pinfunction "D1_E1") (pintype "bidirectional"))
    )
    (net (code "76") (name "unconnected-(U9-NC-PadD6)") (class "Default")
      (node (ref "U9") (pin "D6") (pinfunction "NC_D6") (pintype "no_connect"))
    )
    (net (code "77") (name "unconnected-(U9-STROBE-PadA6)") (class "Default")
      (node (ref "U9") (pin "A6") (pinfunction "STROBE_A6") (pintype "output"))
    )
    (net (code "78") (name "unconnected-(U12-PA0{slash}USART2_CTS{slash}UART4_TX{slash}TIM2_CH1_ETR{slash}WKUP{slash}TIM5_CH1{slash}TIM8_ETR-Pad23)") (class "Default")
      (node (ref "U12") (pin "23") (pinfunction "PA0/USART2_CTS/UART4_TX/TIM2_CH1_ETR/WKUP/TIM5_CH1/TIM8_ETR_23") (pintype "bidirectional"))
    )
    (net (code "79") (name "unconnected-(U12-PA1{slash}USART2_RTS{slash}UART4_RX{slash}TIM5_CH2{slash}TIMM2_CH2{slash}EVENTOUT-Pad24)") (class "Default")
      (node (ref "U12") (pin "24") (pinfunction "PA1/USART2_RTS/UART4_RX/TIM5_CH2/TIMM2_CH2/EVENTOUT_24") (pintype "bidirectional"))
    )
    (net (code "80") (name "unconnected-(U12-PA2{slash}USART2_TX{slash}TIM5_CH3{slash}TIM9_CH1{slash}TIM2_CH3{slash}ETH_MDIO-Pad25)") (class "Default")
      (node (ref "U12") (pin "25") (pinfunction "PA2/USART2_TX/TIM5_CH3/TIM9_CH1/TIM2_CH3/ETH_MDIO_25") (pintype "bidirectional"))
    )
    (net (code "81") (name "unconnected-(U12-PA3{slash}USART2_RX{slash}TIM5_CH4{slash}TIM9_CH2{slash}TIM2_CH4{slash}OTG_HS_ULPI_D0-Pad26)") (class "Default")
      (node (ref "U12") (pin "26") (pinfunction "PA3/USART2_RX/TIM5_CH4/TIM9_CH2/TIM2_CH4/OTG_HS_ULPI_D0_26") (pintype "bidirectional"))
    )
    (net (code "82") (name "unconnected-(U12-PA7{slash}SPI1_MOSI{slash}TIM8_CH1N{slash}TIM14_CH1TIM3_CH2-Pad32)") (class "Default")
      (node (ref "U12") (pin "32") (pinfunction "PA7/SPI1_MOSI/TIM8_CH1N/TIM14_CH1TIM3_CH2_32") (pintype "bidirectional"))
    )
    (net (code "83") (name "unconnected-(U12-PB0{slash}TIM3_CH3{slash}TIM8_CH2N{slash}OTG_HS_ULPI_D1{slash}ETH_MII_RXD2{slash}TIM1_CH2N{slash}-Pad35)") (class "Default")
      (node (ref "U12") (pin "35") (pinfunction "PB0/TIM3_CH3/TIM8_CH2N/OTG_HS_ULPI_D1/ETH_MII_RXD2/TIM1_CH2N/_35") (pintype "bidirectional"))
    )
    (net (code "84") (name "unconnected-(U12-PB1{slash}TIM3_CH4{slash}TIM8_CH3N{slash}OTG_HS_ULPI_D2{slash}ETH_MII_RXD3{slash}OTG_HS_INTN{slash}-Pad36)") (class "Default")
      (node (ref "U12") (pin "36") (pinfunction "PB1/TIM3_CH4/TIM8_CH3N/OTG_HS_ULPI_D2/ETH_MII_RXD3/OTG_HS_INTN/_36") (pintype "bidirectional"))
    )
    (net (code "85") (name "unconnected-(U12-PB3{slash}JTDO{slash}TRACESWO{slash}SPI3_SCK{slash}I2S3_CK{slash}TIM2_CH2{slash}SPI1_SCK-Pad89)") (class "Default")
      (node (ref "U12") (pin "89") (pinfunction "PB3/JTDO/TRACESWO/SPI3_SCK/I2S3_CK/TIM2_CH2/SPI1_SCK_89") (pintype "bidirectional"))
    )
    (net (code "86") (name "unconnected-(U12-PB4{slash}NJTRST{slash}SPI3_MISO{slash}TIM3_CH1{slash}SPI1_MISO{slash}I2S3EXT_SD-Pad90)") (class "Default")
      (node (ref "U12") (pin "90") (pinfunction "PB4/NJTRST/SPI3_MISO/TIM3_CH1/SPI1_MISO/I2S3EXT_SD_90") (pintype "bidirectional"))
    )
    (net (code "87") (name "unconnected-(U12-PC3{slash}SPI2_MOSI{slash}I2S2_SD{slash}OTG_HS_ULPI_NXT{slash}ETH_MII_TX_CLK{slash}ADC123_IN13-Pad18)") (class "Default")
      (node (ref "U12") (pin "18") (pinfunction "PC3/SPI2_MOSI/I2S2_SD/OTG_HS_ULPI_NXT/ETH_MII_TX_CLK/ADC123_IN13_18") (pintype "bidirectional"))
    )
    (net (code "88") (name "unconnected-(U12-PC4{slash}ETH_RMII_RX_D0{slash}ETH_MII_RX_D0{slash}ADC12_IN14-Pad33)") (class "Default")
      (node (ref "U12") (pin "33") (pinfunction "PC4/ETH_RMII_RX_D0/ETH_MII_RX_D0/ADC12_IN14_33") (pintype "bidirectional"))
    )
    (net (code "89") (name "unconnected-(U12-PC5{slash}ETH_RMII_RX_D1{slash}ETH_MII_RX_D1{slash}ADC12_IN15-Pad34)") (class "Default")
      (node (ref "U12") (pin "34") (pinfunction "PC5/ETH_RMII_RX_D1/ETH_MII_RX_D1/ADC12_IN15_34") (pintype "bidirectional"))
    )
    (net (code "90") (name "unconnected-(U12-PC13{slash}RTC_AF1-Pad7)") (class "Default")
      (node (ref "U12") (pin "7") (pinfunction "PC13/RTC_AF1_7") (pintype "bidirectional"))
    )
    (net (code "91") (name "unconnected-(U12-PC14{slash}OSC32_IN-Pad8)") (class "Default")
      (node (ref "U12") (pin "8") (pinfunction "PC14/OSC32_IN_8") (pintype "bidirectional"))
    )
    (net (code "92") (name "unconnected-(U12-PC15{slash}OSC32_OUT-Pad9)") (class "Default")
      (node (ref "U12") (pin "9") (pinfunction "PC15/OSC32_OUT_9") (pintype "bidirectional"))
    )
    (net (code "93") (name "unconnected-(U12-PD0{slash}FSMC_D2{slash}CAN1_RX-Pad81)") (class "Default")
      (node (ref "U12") (pin "81") (pinfunction "PD0/FSMC_D2/CAN1_RX_81") (pintype "bidirectional"))
    )
    (net (code "94") (name "unconnected-(U12-PD1FSMC_D3{slash}CAN1_TX-Pad82)") (class "Default")
      (node (ref "U12") (pin "82") (pinfunction "PD1FSMC_D3/CAN1_TX_82") (pintype "bidirectional"))
    )
    (net (code "95") (name "unconnected-(U12-PD3{slash}FSMC_CLK{slash}USART2_CTS-Pad84)") (class "Default")
      (node (ref "U12") (pin "84") (pinfunction "PD3/FSMC_CLK/USART2_CTS_84") (pintype "bidirectional"))
    )
    (net (code "96") (name "unconnected-(U12-PD4{slash}FSMC_NOE{slash}USART2_RTS-Pad85)") (class "Default")
      (node (ref "U12") (pin "85") (pinfunction "PD4/FSMC_NOE/USART2_RTS_85") (pintype "bidirectional"))
    )
    (net (code "97") (name "unconnected-(U12-PD5{slash}FSMC_NWE{slash}USART2_TX-Pad86)") (class "Default")
      (node (ref "U12") (pin "86") (pinfunction "PD5/FSMC_NWE/USART2_TX_86") (pintype "bidirectional"))
    )
    (net (code "98") (name "unconnected-(U12-PD6{slash}FSMC_NWAIT{slash}USART2_RX-Pad87)") (class "Default")
      (node (ref "U12") (pin "87") (pinfunction "PD6/FSMC_NWAIT/USART2_RX_87") (pintype "bidirectional"))
    )
    (net (code "99") (name "unconnected-(U12-PD7{slash}USART2_CK{slash}FSMC_NE1{slash}FSMC_NCE2-Pad88)") (class "Default")
      (node (ref "U12") (pin "88") (pinfunction "PD7/USART2_CK/FSMC_NE1/FSMC_NCE2_88") (pintype "bidirectional"))
    )
    (net (code "100") (name "unconnected-(U12-PD10{slash}FSMC_D15{slash}USART3_CK-Pad57)") (class "Default")
      (node (ref "U12") (pin "57") (pinfunction "PD10/FSMC_D15/USART3_CK_57") (pintype "bidirectional"))
    )
    (net (code "101") (name "unconnected-(U12-PD11{slash}FSMC_A16{slash}USART3_CTS-Pad58)") (class "Default")
      (node (ref "U12") (pin "58") (pinfunction "PD11/FSMC_A16/USART3_CTS_58") (pintype "bidirectional"))
    )
    (net (code "102") (name "unconnected-(U12-PD14{slash}FSMC_D0{slash}TIM4_CH3-Pad61)") (class "Default")
      (node (ref "U12") (pin "61") (pinfunction "PD14/FSMC_D0/TIM4_CH3_61") (pintype "bidirectional"))
    )
    (net (code "103") (name "unconnected-(U12-PD15{slash}FSMC_D1{slash}TIM4_CH4-Pad62)") (class "Default")
      (node (ref "U12") (pin "62") (pinfunction "PD15/FSMC_D1/TIM4_CH4_62") (pintype "bidirectional"))
    )
    (net (code "104") (name "unconnected-(U12-PE3{slash}TRACED0{slash}FSMC_A19-Pad2)") (class "Default")
      (node (ref "U12") (pin "2") (pinfunction "PE3/TRACED0/FSMC_A19_2") (pintype "bidirectional"))
    )
    (net (code "105") (name "unconnected-(U12-PE7{slash}FSMC_D4{slash}TIM1_ETR-Pad38)") (class "Default")
      (node (ref "U12") (pin "38") (pinfunction "PE7/FSMC_D4/TIM1_ETR_38") (pintype "bidirectional"))
    )
    (net (code "106") (name "unconnected-(U12-PE8{slash}FSMC_D5{slash}TIM1_CH1N-Pad39)") (class "Default")
      (node (ref "U12") (pin "39") (pinfunction "PE8/FSMC_D5/TIM1_CH1N_39") (pintype "bidirectional"))
    )
    (net (code "107") (name "unconnected-(U12-PE9{slash}FSMC_D6{slash}TIM1_CH1-Pad40)") (class "Default")
      (node (ref "U12") (pin "40") (pinfunction "PE9/FSMC_D6/TIM1_CH1_40") (pintype "bidirectional"))
    )
    (net (code "108") (name "unconnected-(U12-PE10{slash}FSMC_D7{slash}TIM1_CH2N-Pad41)") (class "Default")
      (node (ref "U12") (pin "41") (pinfunction "PE10/FSMC_D7/TIM1_CH2N_41") (pintype "bidirectional"))
    )
    (net (code "109") (name "unconnected-(U12-PE11{slash}FSMC_D8{slash}TIM1_CH2-Pad42)") (class "Default")
      (node (ref "U12") (pin "42") (pinfunction "PE11/FSMC_D8/TIM1_CH2_42") (pintype "bidirectional"))
    )
    (net (code "110") (name "unconnected-(U12-PE12{slash}FSMC_D9{slash}TIM1_CH3N-Pad43)") (class "Default")
      (node (ref "U12") (pin "43") (pinfunction "PE12/FSMC_D9/TIM1_CH3N_43") (pintype "bidirectional"))
    )
    (net (code "111") (name "unconnected-(U12-PE13{slash}FSMC_D10{slash}TIM1_CH3-Pad44)") (class "Default")
      (node (ref "U12") (pin "44") (pinfunction "PE13/FSMC_D10/TIM1_CH3_44") (pintype "bidirectional"))
    )
    (net (code "112") (name "unconnected-(U12-PE14{slash}FSMC_D11{slash}TIM1_CH4-Pad45)") (class "Default")
      (node (ref "U12") (pin "45") (pinfunction "PE14/FSMC_D11/TIM1_CH4_45") (pintype "bidirectional"))
    )
    (net (code "113") (name "unconnected-(U12-PE15FSMC_D12{slash}TIM1_BKIN-Pad46)") (class "Default")
      (node (ref "U12") (pin "46") (pinfunction "PE15FSMC_D12/TIM1_BKIN_46") (pintype "bidirectional"))
    )
    (net (code "114") (name "unconnected-(X2-GND1-PadMT1)") (class "Default")
      (node (ref "X2") (pin "MT1") (pinfunction "GND1_MT1") (pintype "passive"))
    )
    (net (code "115") (name "unconnected-(X2-GND2-PadMT2)") (class "Default")
      (node (ref "X2") (pin "MT2") (pinfunction "GND2_MT2") (pintype "passive"))
    )
    (net (code "116") (name "unconnected-(X2-GND3-PadMT5)") (class "Default")
      (node (ref "X2") (pin "MT5") (pinfunction "GND3_MT5") (pintype "passive"))
    )
    (net (code "117") (name "unconnected-(X2-GND4-PadMT6)") (class "Default")
      (node (ref "X2") (pin "MT6") (pinfunction "GND4_MT6") (pintype "passive"))
    )
  )
)
